# SWD-NEEDLE.net
KiCad netlist of a schematic drawn in Altium Designer
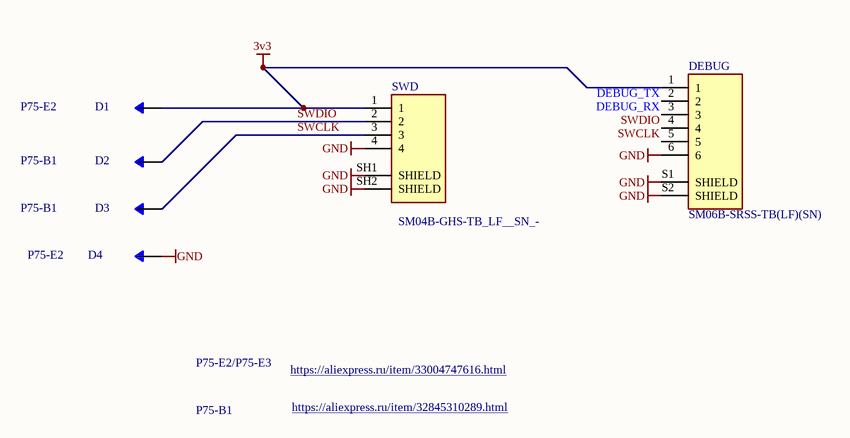
[diagram p0: SWD-NEEDLE.SchDoc]

(export (version "E")
  (design (tool "Eeschema 10.0.6"))
  (components
    (comp (ref "D1")
      (value "P75-E2")
      (footprint "P75-E2")
      (description "Pogo pin P75-E2")
      (fields (field (name "MP") "P75-B1"))
      (libsource (lib "lib") (part "Pogo pin P75-E2"))
    )
    (comp (ref "D2")
      (value "P75-B1")
      (footprint "P75-E2")
      (description "Pogo pin P75-B1")
      (libsource (lib "lib") (part "Pogo pin P75-E2"))
    )
    (comp (ref "D3")
      (value "P75-B1")
      (footprint "P75-E2")
      (description "Pogo pin P75-B1")
      (libsource (lib "lib") (part "Pogo pin P75-E2"))
    )
    (comp (ref "D4")
      (value "P75-E2")
      (footprint "P75-E2")
      (description "Pogo pin P75-E2")
      (fields (field (name "MP") "P75-B1"))
      (libsource (lib "lib") (part "Pogo pin P75-E2"))
    )
    (comp (ref "DEBUG")
      (value "SM06B-SRSS-TB(LF)(SN)")
      (footprint "JST_SM06B-SRSS-TB(LF)(SN)")
      (description "Connector Header Surface Mount, Right Angle 6 position 0.039 _1.00mm_")
      (fields
        (field (name "MP") "SM06B-SRSS-TB_LF__SN_")
        (field (name "DIGI-KEY_PART_NUMBER") "455-1806-1-ND")
      )
      (libsource (lib "lib") (part "SM06B-SRSS-TB(LF)(SN)"))
    )
    (comp (ref "SWD")
      (value "~")
      (footprint "JST_SM04B-GHS-TB(LF)(SN)-")
      (description "Connector Header Surface Mount, Right Angle 4 position 0.049 _1.25mm_")
      (fields (field (name "MP") "SM04B-GHS-TB_LF__SN_-") (field (name "MF") "JST Sales"))
      (libsource (lib "lib") (part "SM04B-GHS-TB(LF)(SN)-"))
    )
  )
  (nets
    (net (code "1") (name "/DEBUG_RX") (class "Default")
      (node (ref "DEBUG") (pin "3") (pinfunction "3_3") (pintype "passive"))
    )
    (net (code "2") (name "/DEBUG_TX") (class "Default")
      (node (ref "DEBUG") (pin "2") (pinfunction "2_2") (pintype "passive"))
    )
    (net (code "3") (name "/SWCLK") (class "Default")
      (node (ref "D3") (pin "1") (pinfunction "1_1") (pintype "passive"))
      (node (ref "DEBUG") (pin "5") (pinfunction "5_5") (pintype "passive"))
      (node (ref "SWD") (pin "3") (pinfunction "3_3") (pintype "passive"))
    )
    (net (code "4") (name "/SWDIO") (class "Default")
      (node (ref "D2") (pin "1") (pinfunction "1_1") (pintype "passive"))
      (node (ref "DEBUG") (pin "4") (pinfunction "4_4") (pintype "passive"))
      (node (ref "SWD") (pin "2") (pinfunction "2_2") (pintype "passive"))
    )
    (net (code "5") (name "3v3") (class "Default")
      (node (ref "D1") (pin "1") (pinfunction "1_1") (pintype "passive"))
      (node (ref "DEBUG") (pin "1") (pinfunction "1_1") (pintype "passive"))
      (node (ref "SWD") (pin "1") (pinfunction "1_1") (pintype "passive"))
    )
    (net (code "6") (name "GND") (class "Default")
      (node (ref "D4") (pin "1") (pinfunction "1_1") (pintype "passive"))
      (node (ref "DEBUG") (pin "6") (pinfunction "6_6") (pintype "passive"))
      (node (ref "DEBUG") (pin "S1") (pinfunction "SHIELD_S1") (pintype "passive"))
      (node (ref "DEBUG") (pin "S2") (pinfunction "SHIELD_S2") (pintype "passive"))
      (node (ref "SWD") (pin "4") (pinfunction "4_4") (pintype "passive"))
      (node (ref "SWD") (pin "SH1") (pinfunction "SHIELD_SH1") (pintype "power_in"))
      (node (ref "SWD") (pin "SH2") (pinfunction "SHIELD_SH2") (pintype "power_in"))
    )
  )
)
